# Connectors.net
KiCad netlist of a schematic drawn in Altium Designer
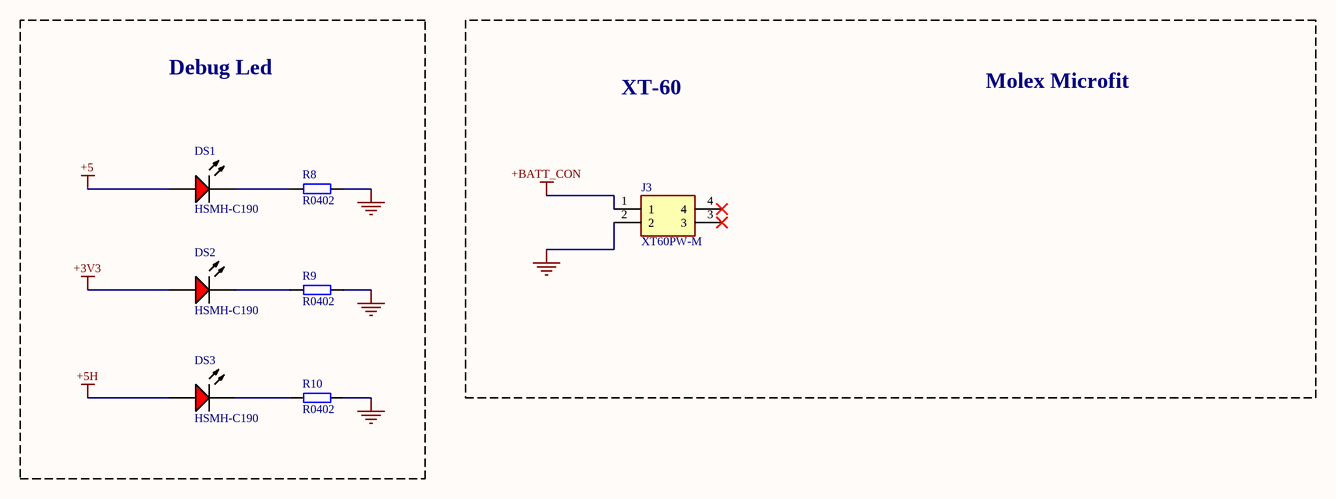
[diagram p0: Connectors.SchDoc]

(export (version "E")
  (design (tool "Eeschema 10.0.6"))
  (components
    (comp (ref "DS1")
      (value "HSMH-C190")
      (footprint "AVAG-HSMX-C190_V")
      (description "LED Uni-Color Red, 65 mW, 20 mA, -40 to 85 degC, 2-Pin SMD, RoHS, Tape and Reel")
      (fields (field (name "POWER") "78mW") (field (name "MANUFACTURER") "Avago"))
      (libsource (lib "Shravan Talapady") (part "LED-RED-AK-2"))
    )
    (comp (ref "DS2")
      (value "HSMH-C190")
      (footprint "AVAG-HSMX-C190_V")
      (description "LED Uni-Color Red, 65 mW, 20 mA, -40 to 85 degC, 2-Pin SMD, RoHS, Tape and Reel")
      (fields (field (name "POWER") "78mW") (field (name "MANUFACTURER") "Avago"))
      (libsource (lib "Shravan Talapady") (part "LED-RED-AK-2"))
    )
    (comp (ref "DS3")
      (value "HSMH-C190")
      (footprint "AVAG-HSMX-C190_V")
      (description "LED Uni-Color Red, 65 mW, 20 mA, -40 to 85 degC, 2-Pin SMD, RoHS, Tape and Reel")
      (fields (field (name "POWER") "78mW") (field (name "MANUFACTURER") "Avago"))
      (libsource (lib "Shravan Talapady") (part "LED-RED-AK-2"))
    )
    (comp (ref "J3")
      (value "XT60PW-M")
      (footprint "SamacSys:XT60PWM")
      (description "Connector")
      (libsource (lib "Powersch") (part "XT60PW-M"))
    )
    (comp (ref "R8")
      (value "R0402")
      (footprint "RES_0402")
      (description "Resistor SMD 0402")
      (libsource (lib "Powersch") (part "RES_0402"))
    )
    (comp (ref "R9")
      (value "R0402")
      (footprint "RES_0402")
      (description "Resistor SMD 0402")
      (libsource (lib "Powersch") (part "RES_0402"))
    )
    (comp (ref "R10")
      (value "R0402")
      (footprint "RES_0402")
      (description "Resistor SMD 0402")
      (libsource (lib "Powersch") (part "RES_0402"))
    )
  )
  (nets
    (net (code "1") (name "+3V3") (class "Default")
      (node (ref "DS2") (pin "1") (pinfunction "A_1") (pintype "passive"))
    )
    (net (code "2") (name "+5") (class "Default")
      (node (ref "DS1") (pin "1") (pinfunction "A_1") (pintype "passive"))
    )
    (net (code "3") (name "+5H") (class "Default")
      (node (ref "DS3") (pin "1") (pinfunction "A_1") (pintype "passive"))
    )
    (net (code "4") (name "+BATT_CON") (class "Default")
      (node (ref "J3") (pin "1") (pinfunction "1_1") (pintype "passive"))
    )
    (net (code "5") (name "GND") (class "Default")
      (node (ref "J3") (pin "2") (pinfunction "2_2") (pintype "passive"))
      (node (ref "R10") (pin "2") (pinfunction "2_2") (pintype "passive"))
      (node (ref "R8") (pin "2") (pinfunction "2_2") (pintype "passive"))
      (node (ref "R9") (pin "2") (pinfunction "2_2") (pintype "passive"))
    )
    (net (code "6") (name "Net-(DS1-K)") (class "Default")
      (node (ref "DS1") (pin "2") (pinfunction "K_2") (pintype "passive"))
      (node (ref "R8") (pin "1") (pinfunction "1_1") (pintype "passive"))
    )
    (net (code "7") (name "Net-(DS2-K)") (class "Default")
      (node (ref "DS2") (pin "2") (pinfunction "K_2") (pintype "passive"))
      (node (ref "R9") (pin "1") (pinfunction "1_1") (pintype "passive"))
    )
    (net (code "8") (name "Net-(DS3-K)") (class "Default")
      (node (ref "DS3") (pin "2") (pinfunction "K_2") (pintype "passive"))
      (node (ref "R10") (pin "1") (pinfunction "1_1") (pintype "passive"))
    )
    (net (code "9") (name "unconnected-(J3-Pad3)") (class "Default")
      (node (ref "J3") (pin "3") (pinfunction "3_3") (pintype "passive+no_connect"))
    )
    (net (code "10") (name "unconnected-(J3-Pad4)") (class "Default")
      (node (ref "J3") (pin "4") (pinfunction "4_4") (pintype "passive+no_connect"))
    )
  )
)
